# Sheet7.net
KiCad netlist of a schematic drawn in Altium Designer
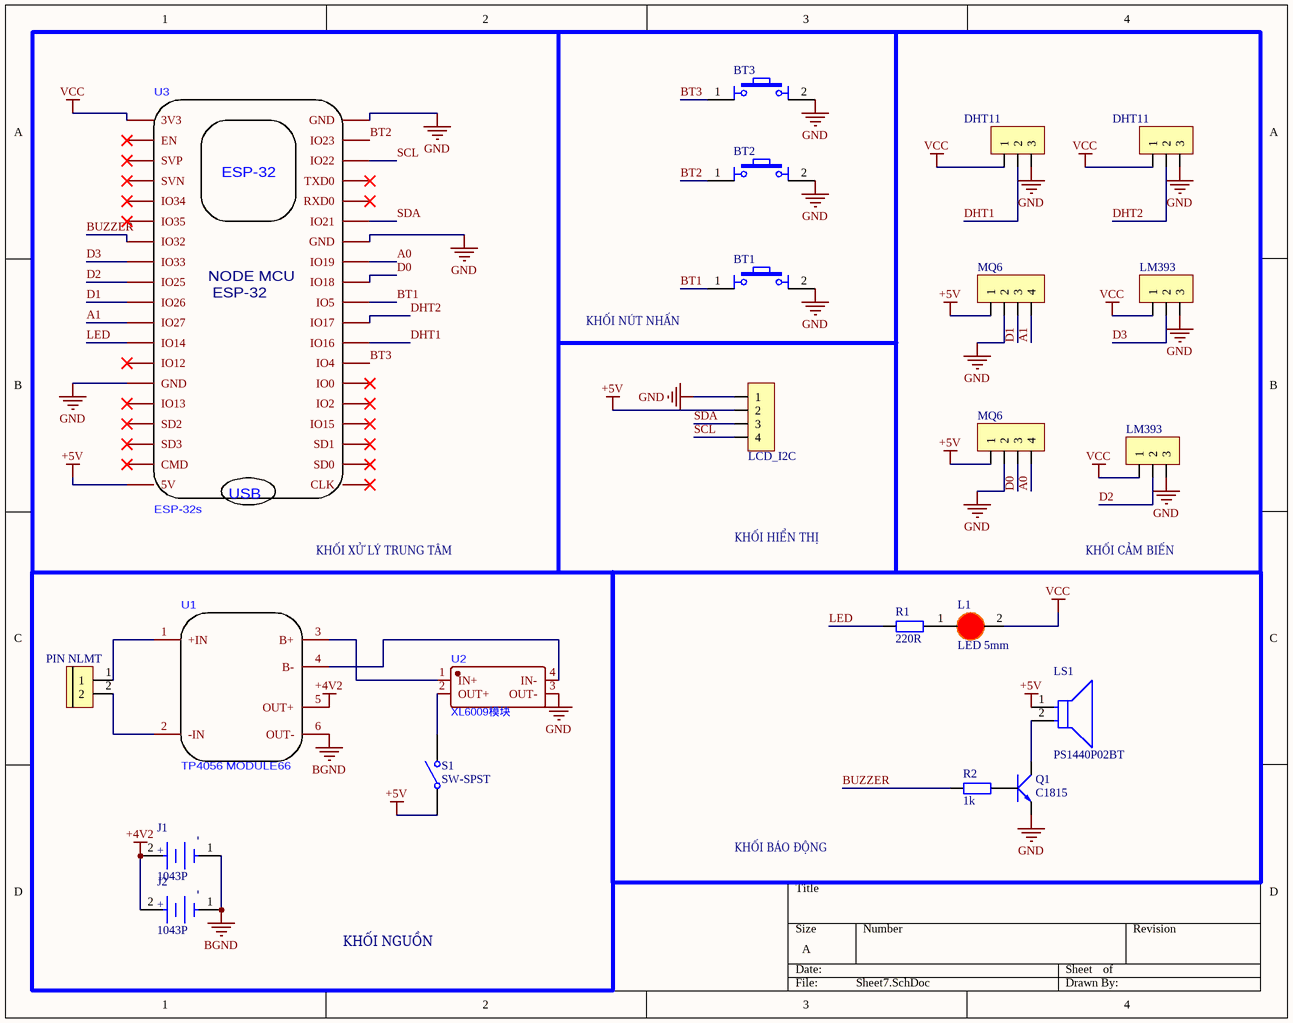
[diagram p0: Sheet7.SchDoc]

(export (version "E")
  (design (tool "Eeschema 10.0.6"))
  (components
    (comp (ref "BT1")
      (value "Nut Nhan 4 Chan Cam 6x6")
      (footprint "Nut Nhan 4 Chan Cam 6x6")
      (description "Nut Nhan 4 Chan 6x6mm")
      (libsource (lib "thuvien") (part "Nut Nhan 4 Chan Cam 6x6"))
    )
    (comp (ref "BT2")
      (value "Nut Nhan 4 Chan Cam 6x6")
      (footprint "Nut Nhan 4 Chan Cam 6x6")
      (description "Nut Nhan 4 Chan 6x6mm")
      (libsource (lib "thuvien") (part "Nut Nhan 4 Chan Cam 6x6"))
    )
    (comp (ref "BT3")
      (value "Nut Nhan 4 Chan Cam 6x6")
      (footprint "Nut Nhan 4 Chan Cam 6x6")
      (description "Nut Nhan 4 Chan 6x6mm")
      (libsource (lib "thuvien") (part "Nut Nhan 4 Chan Cam 6x6"))
    )
    (comp (ref "J1")
      (value "1043P")
      (footprint "FP-1043P-MFG")
      (description "BATT HOLDER 18650 1 CELL PC PIN")
      (libsource (lib "Altium Content Vault") (part "60d3b5b901a8747834971d0eb8cf3fd"))
    )
    (comp (ref "J2")
      (value "1043P")
      (footprint "FP-1043P-MFG")
      (description "BATT HOLDER 18650 1 CELL PC PIN")
      (libsource (lib "Altium Content Vault") (part "60d3b5b901a8747834971d0eb8cf3fd"))
    )
    (comp (ref "JP1")
      (value "DHT11")
      (footprint "JP 1x3 DT")
      (description "Cắm")
      (libsource (lib "thuvien") (part "JP 1x3 2.54 Duc Thang"))
    )
    (comp (ref "JP2")
      (value "DHT11")
      (footprint "JP 1x3 DT")
      (description "Cắm")
      (libsource (lib "thuvien") (part "JP 1x3 2.54 Duc Thang"))
    )
    (comp (ref "JP3")
      (value "MQ6")
      (footprint "JP 1x4 DT")
      (description "Cắm")
      (libsource (lib "thuvien") (part "JP 1x4 2.54 Duc Thang"))
    )
    (comp (ref "JP4")
      (value "LM393")
      (footprint "JP 1x3 DT")
      (description "Cắm")
      (libsource (lib "thuvien") (part "JP 1x3 2.54 Duc Thang"))
    )
    (comp (ref "JP5")
      (value "LCD_I2C")
      (footprint "JP 1x4 DT")
      (description "Cắm")
      (libsource (lib "") (part "JP 1x4 2.54 Duc Thang_1"))
    )
    (comp (ref "JP6")
      (value "MQ6")
      (footprint "JP 1x4 DT")
      (description "Cắm")
      (libsource (lib "thuvien") (part "JP 1x4 2.54 Duc Thang"))
    )
    (comp (ref "JP7")
      (value "LM393")
      (footprint "JP 1x3 DT")
      (description "Cắm")
      (libsource (lib "thuvien") (part "JP 1x3 2.54 Duc Thang"))
    )
    (comp (ref "L1")
      (value "LED 5mm")
      (footprint "LED-5MM-RED")
      (description "Cắm")
      (libsource (lib "thuvien") (part "LED 5mm Do"))
    )
    (comp (ref "LS1")
      (value "PS1440P02BT")
      (footprint "FP-PS1440P02BT-MFG")
      (description "AUDIO PIEZO TRANSDUCER 30V TH")
      (libsource (lib "Altium Content Vault") (part "5f581d31613f872430949aa526fd155"))
    )
    (comp (ref "PIN NLMT")
      (value "CON 2 KF301")
      (footprint "Con 2 KF301 5.08")
      (description "Cắm")
      (libsource (lib "thuvien") (part "CON 2 KF301"))
    )
    (comp (ref "Q1")
      (value "C1815")
      (footprint "TO92")
      (description "NPN transistor")
      (libsource (lib "thuvien") (part "C1815"))
    )
    (comp (ref "R1")
      (value "220R")
      (footprint "tro vach 1/4w")
      (description "Cắm")
      (libsource (lib "thuvien") (part "Tro Vach 1/4W 5% 220R"))
    )
    (comp (ref "R2")
      (value "1k")
      (footprint "tro vach 1/4w")
      (description "Cắm")
      (libsource (lib "thuvien") (part "Tro Vach 1/4W 5% 1k"))
    )
    (comp (ref "S1")
      (value "SW-SPST")
      (footprint "SPST-2")
      (description "Single-Pole, Single-Throw Switch")
      (fields (field (name "PUBLISHER") "Altium Limited"))
      (libsource (lib "Miscellaneous Devices") (part "SW-SPST"))
    )
    (comp (ref "U1")
      (value "TP4056 MODULE66")
      (footprint "TP4056MODULE")
      (libsource (lib "thuvien") (part "TP4056 MODULE66"))
    )
    (comp (ref "U2")
      (value "XL6009模块")
      (footprint "XFMR-SMD_XL6009")
      (libsource (lib "XL6009模块_2025-05-11") (part "XL6009模块"))
    )
    (comp (ref "U3")
      (value "ESP-32s")
      (footprint "ESP-32S_2025-05-07:ESP-32S")
      (libsource (lib "ESP-32s_2025-05-07") (part "ESP-32s"))
    )
  )
  (nets
    (net (code "1") (name "+4V2") (class "Default")
      (node (ref "J1") (pin "2") (pinfunction "A_2") (pintype "passive"))
      (node (ref "J2") (pin "2") (pinfunction "A_2") (pintype "passive"))
      (node (ref "U1") (pin "5") (pinfunction "OUT+_5") (pintype "passive"))
    )
    (net (code "2") (name "+5V") (class "Default")
      (node (ref "JP3") (pin "1") (pinfunction "1_1") (pintype "passive"))
      (node (ref "JP5") (pin "2") (pinfunction "2_2") (pintype "passive"))
      (node (ref "JP6") (pin "1") (pinfunction "1_1") (pintype "passive"))
      (node (ref "LS1") (pin "1") (pinfunction "1_1") (pintype "passive"))
      (node (ref "S1") (pin "1") (pinfunction "COMMON_1") (pintype "passive"))
      (node (ref "U3") (pin "19") (pinfunction "5V_19") (pintype "passive"))
    )
    (net (code "3") (name "/A0") (class "Default")
      (node (ref "JP6") (pin "4") (pinfunction "4_4") (pintype "passive"))
      (node (ref "U3") (pin "31") (pinfunction "IO19_31") (pintype "passive"))
    )
    (net (code "4") (name "/A1") (class "Default")
      (node (ref "JP3") (pin "4") (pinfunction "4_4") (pintype "passive"))
      (node (ref "U3") (pin "11") (pinfunction "IO27_11") (pintype "passive"))
    )
    (net (code "5") (name "/BT1") (class "Default")
      (node (ref "BT1") (pin "1") (pintype "passive"))
      (node (ref "U3") (pin "29") (pinfunction "IO5_29") (pintype "passive"))
    )
    (net (code "6") (name "/BT2") (class "Default")
      (node (ref "BT2") (pin "1") (pintype "passive"))
      (node (ref "U3") (pin "37") (pinfunction "IO23_37") (pintype "passive"))
    )
    (net (code "7") (name "/BT3") (class "Default")
      (node (ref "BT3") (pin "1") (pintype "passive"))
      (node (ref "U3") (pin "26") (pinfunction "IO4_26") (pintype "passive"))
    )
    (net (code "8") (name "/BUZZER") (class "Default")
      (node (ref "R2") (pin "1") (pinfunction "1_1") (pintype "passive"))
      (node (ref "U3") (pin "7") (pinfunction "IO32_7") (pintype "passive"))
    )
    (net (code "9") (name "/D0") (class "Default")
      (node (ref "JP6") (pin "3") (pinfunction "3_3") (pintype "passive"))
      (node (ref "U3") (pin "30") (pinfunction "IO18_30") (pintype "passive"))
    )
    (net (code "10") (name "/D1") (class "Default")
      (node (ref "JP3") (pin "3") (pinfunction "3_3") (pintype "passive"))
      (node (ref "U3") (pin "10") (pinfunction "IO26_10") (pintype "passive"))
    )
    (net (code "11") (name "/D2") (class "Default")
      (node (ref "JP7") (pin "2") (pinfunction "2_2") (pintype "passive"))
      (node (ref "U3") (pin "9") (pinfunction "IO25_9") (pintype "passive"))
    )
    (net (code "12") (name "/D3") (class "Default")
      (node (ref "JP4") (pin "2") (pinfunction "2_2") (pintype "passive"))
      (node (ref "U3") (pin "8") (pinfunction "IO33_8") (pintype "passive"))
    )
    (net (code "13") (name "/DHT1") (class "Default")
      (node (ref "JP1") (pin "2") (pinfunction "2_2") (pintype "passive"))
      (node (ref "U3") (pin "27") (pinfunction "IO16_27") (pintype "passive"))
    )
    (net (code "14") (name "/DHT2") (class "Default")
      (node (ref "JP2") (pin "2") (pinfunction "2_2") (pintype "passive"))
      (node (ref "U3") (pin "28") (pinfunction "IO17_28") (pintype "passive"))
    )
    (net (code "15") (name "/LED") (class "Default")
      (node (ref "R1") (pin "1") (pinfunction "1_1") (pintype "passive"))
      (node (ref "U3") (pin "12") (pinfunction "IO14_12") (pintype "passive"))
    )
    (net (code "16") (name "/SCL") (class "Default")
      (node (ref "JP5") (pin "4") (pinfunction "4_4") (pintype "passive"))
      (node (ref "U3") (pin "36") (pinfunction "IO22_36") (pintype "passive"))
    )
    (net (code "17") (name "/SDA") (class "Default")
      (node (ref "JP5") (pin "3") (pinfunction "3_3") (pintype "passive"))
      (node (ref "U3") (pin "33") (pinfunction "IO21_33") (pintype "passive"))
    )
    (net (code "18") (name "BGND") (class "Default")
      (node (ref "J1") (pin "1") (pinfunction "C_1") (pintype "passive"))
      (node (ref "J2") (pin "1") (pinfunction "C_1") (pintype "passive"))
      (node (ref "U1") (pin "6") (pinfunction "OUT-_6") (pintype "passive"))
    )
    (net (code "19") (name "GND") (class "Default")
      (node (ref "BT1") (pin "2") (pintype "passive"))
      (node (ref "BT2") (pin "2") (pintype "passive"))
      (node (ref "BT3") (pin "2") (pintype "passive"))
      (node (ref "JP1") (pin "3") (pinfunction "3_3") (pintype "passive"))
      (node (ref "JP2") (pin "3") (pinfunction "3_3") (pintype "passive"))
      (node (ref "JP3") (pin "2") (pinfunction "2_2") (pintype "passive"))
      (node (ref "JP4") (pin "3") (pinfunction "3_3") (pintype "passive"))
      (node (ref "JP5") (pin "1") (pinfunction "1_1") (pintype "passive"))
      (node (ref "JP6") (pin "2") (pinfunction "2_2") (pintype "passive"))
      (node (ref "JP7") (pin "3") (pinfunction "3_3") (pintype "passive"))
      (node (ref "Q1") (pin "1") (pinfunction "E_1") (pintype "passive"))
      (node (ref "U2") (pin "3") (pinfunction "OUT-_3") (pintype "passive"))
      (node (ref "U3") (pin "14") (pinfunction "GND_14") (pintype "passive"))
      (node (ref "U3") (pin "32") (pinfunction "GND_32") (pintype "passive"))
      (node (ref "U3") (pin "38") (pinfunction "GND_38") (pintype "passive"))
    )
    (net (code "20") (name "Net-(L1-A)") (class "Default")
      (node (ref "L1") (pin "1") (pinfunction "A_1") (pintype "passive"))
      (node (ref "R1") (pin "2") (pinfunction "2_2") (pintype "passive"))
    )
    (net (code "21") (name "Net-(Q1-B)") (class "Default")
      (node (ref "Q1") (pin "3") (pinfunction "B_3") (pintype "passive"))
      (node (ref "R2") (pin "2") (pinfunction "2_2") (pintype "passive"))
    )
    (net (code "22") (name "Net-(Q1-C)") (class "Default")
      (node (ref "LS1") (pin "2") (pinfunction "2_2") (pintype "passive"))
      (node (ref "Q1") (pin "2") (pinfunction "C_2") (pintype "passive"))
    )
    (net (code "23") (name "Net-(S1-NO)") (class "Default")
      (node (ref "S1") (pin "2") (pinfunction "NO_2") (pintype "passive"))
      (node (ref "U2") (pin "2") (pinfunction "OUT+_2") (pintype "passive"))
    )
    (net (code "24") (name "Net-(U1-+IN)") (class "Default")
      (node (ref "PIN NLMT") (pin "1") (pinfunction "1_1") (pintype "passive"))
      (node (ref "U1") (pin "1") (pinfunction "+IN_1") (pintype "passive"))
    )
    (net (code "25") (name "Net-(U1--IN)") (class "Default")
      (node (ref "PIN NLMT") (pin "2") (pinfunction "2_2") (pintype "passive"))
      (node (ref "U1") (pin "2") (pinfunction "-IN_2") (pintype "passive"))
    )
    (net (code "26") (name "Net-(U1-B+)") (class "Default")
      (node (ref "U1") (pin "3") (pinfunction "B+_3") (pintype "passive"))
      (node (ref "U2") (pin "1") (pinfunction "IN+_1") (pintype "passive"))
    )
    (net (code "27") (name "Net-(U1-B-)") (class "Default")
      (node (ref "U1") (pin "4") (pinfunction "B-_4") (pintype "passive"))
      (node (ref "U2") (pin "4") (pinfunction "IN-_4") (pintype "passive"))
    )
    (net (code "28") (name "VCC") (class "Default")
      (node (ref "JP1") (pin "1") (pinfunction "1_1") (pintype "passive"))
      (node (ref "JP2") (pin "1") (pinfunction "1_1") (pintype "passive"))
      (node (ref "JP4") (pin "1") (pinfunction "1_1") (pintype "passive"))
      (node (ref "JP7") (pin "1") (pinfunction "1_1") (pintype "passive"))
      (node (ref "L1") (pin "2") (pinfunction "K_2") (pintype "passive"))
      (node (ref "U3") (pin "1") (pinfunction "3V3_1") (pintype "passive"))
    )
    (net (code "29") (name "unconnected-(U3-CLK-Pad20)") (class "Default")
      (node (ref "U3") (pin "20") (pinfunction "CLK_20") (pintype "passive+no_connect"))
    )
    (net (code "30") (name "unconnected-(U3-CMD-Pad18)") (class "Default")
      (node (ref "U3") (pin "18") (pinfunction "CMD_18") (pintype "passive+no_connect"))
    )
    (net (code "31") (name "unconnected-(U3-EN-Pad2)") (class "Default")
      (node (ref "U3") (pin "2") (pinfunction "EN_2") (pintype "passive+no_connect"))
    )
    (net (code "32") (name "unconnected-(U3-IO0-Pad25)") (class "Default")
      (node (ref "U3") (pin "25") (pinfunction "IO0_25") (pintype "passive+no_connect"))
    )
    (net (code "33") (name "unconnected-(U3-IO2-Pad24)") (class "Default")
      (node (ref "U3") (pin "24") (pinfunction "IO2_24") (pintype "passive+no_connect"))
    )
    (net (code "34") (name "unconnected-(U3-IO12-Pad13)") (class "Default")
      (node (ref "U3") (pin "13") (pinfunction "IO12_13") (pintype "passive+no_connect"))
    )
    (net (code "35") (name "unconnected-(U3-IO13-Pad15)") (class "Default")
      (node (ref "U3") (pin "15") (pinfunction "IO13_15") (pintype "passive+no_connect"))
    )
    (net (code "36") (name "unconnected-(U3-IO15-Pad23)") (class "Default")
      (node (ref "U3") (pin "23") (pinfunction "IO15_23") (pintype "passive+no_connect"))
    )
    (net (code "37") (name "unconnected-(U3-IO34-Pad5)") (class "Default")
      (node (ref "U3") (pin "5") (pinfunction "IO34_5") (pintype "passive+no_connect"))
    )
    (net (code "38") (name "unconnected-(U3-IO35-Pad6)") (class "Default")
      (node (ref "U3") (pin "6") (pinfunction "IO35_6") (pintype "passive+no_connect"))
    )
    (net (code "39") (name "unconnected-(U3-RXD0-Pad34)") (class "Default")
      (node (ref "U3") (pin "34") (pinfunction "RXD0_34") (pintype "passive+no_connect"))
    )
    (net (code "40") (name "unconnected-(U3-SD0-Pad21)") (class "Default")
      (node (ref "U3") (pin "21") (pinfunction "SD0_21") (pintype "passive+no_connect"))
    )
    (net (code "41") (name "unconnected-(U3-SD1-Pad22)") (class "Default")
      (node (ref "U3") (pin "22") (pinfunction "SD1_22") (pintype "passive+no_connect"))
    )
    (net (code "42") (name "unconnected-(U3-SD2-Pad16)") (class "Default")
      (node (ref "U3") (pin "16") (pinfunction "SD2_16") (pintype "passive+no_connect"))
    )
    (net (code "43") (name "unconnected-(U3-SD3-Pad17)") (class "Default")
      (node (ref "U3") (pin "17") (pinfunction "SD3_17") (pintype "passive+no_connect"))
    )
    (net (code "44") (name "unconnected-(U3-SVN-Pad4)") (class "Default")
      (node (ref "U3") (pin "4") (pinfunction "SVN_4") (pintype "passive+no_connect"))
    )
    (net (code "45") (name "unconnected-(U3-SVP-Pad3)") (class "Default")
      (node (ref "U3") (pin "3") (pinfunction "SVP_3") (pintype "passive+no_connect"))
    )
    (net (code "46") (name "unconnected-(U3-TXD0-Pad35)") (class "Default")
      (node (ref "U3") (pin "35") (pinfunction "TXD0_35") (pintype "passive+no_connect"))
    )
  )
)
